# 12VDCDC.net
KiCad netlist of a schematic drawn in EAGLE
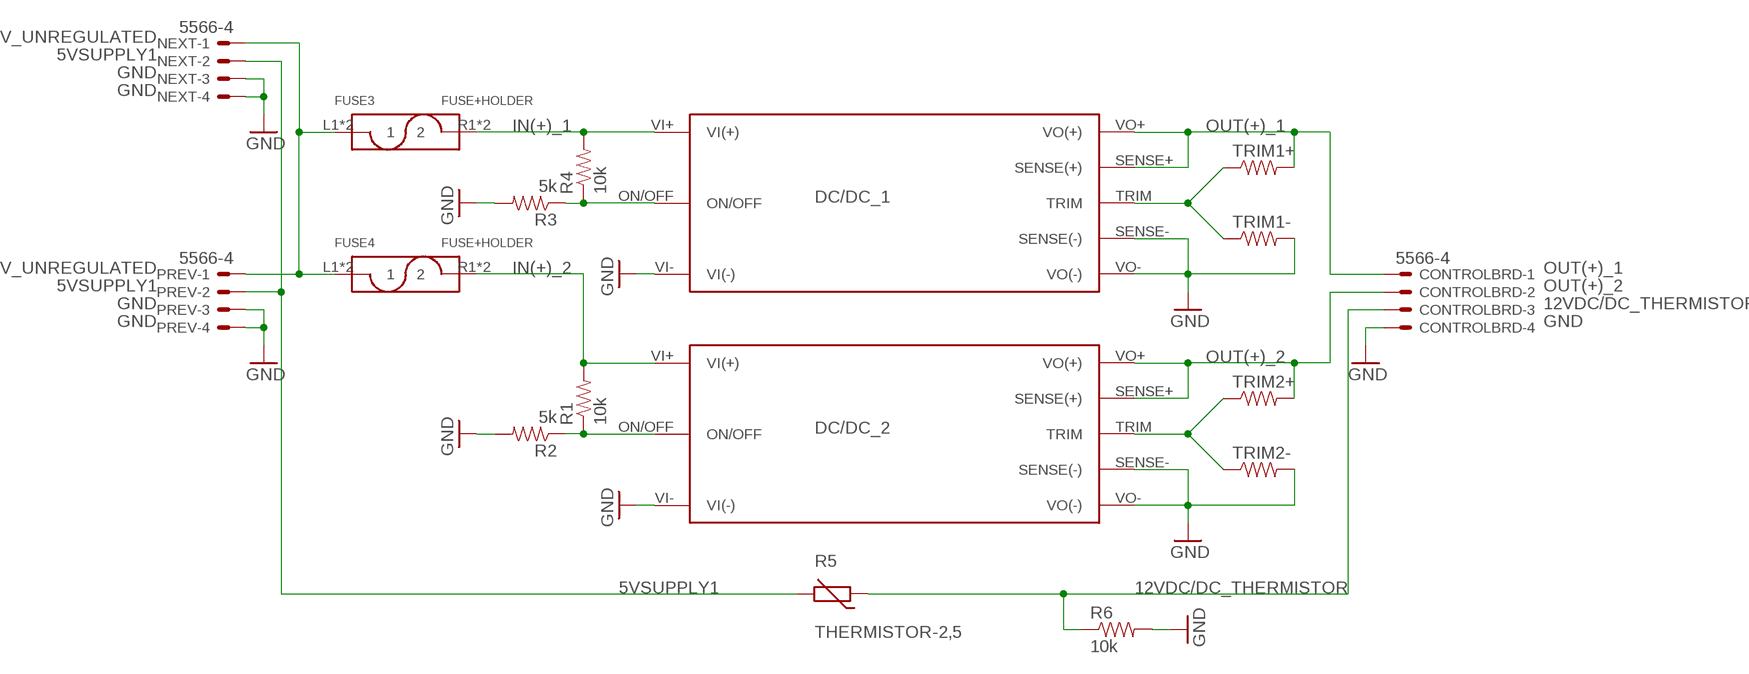
[diagram p0: schematic, sheet 1]

(export (version "E")
  (design (tool "Eeschema 10.0.6"))
  (components
    (comp (ref "CONTROLBRD")
      (value "5566-4")
      (footprint "eagle-import:5566-4")
      (libsource (lib "eagle-import") (part "5566-4"))
    )
    (comp (ref "DC/DC_1")
      (value "DC/DC-EIGHTH_BRICKEHHD006A0B41-HZ")
      (footprint "eagle-import:DC_DC-EIGHTH_BRICK")
      (libsource (lib "eagle-import") (part "DC/DC-EIGHTH_BRICKEHHD006A0B41-HZ"))
    )
    (comp (ref "DC/DC_2")
      (value "DC/DC-EIGHTH_BRICKEHHD006A0B41-HZ")
      (footprint "eagle-import:DC_DC-EIGHTH_BRICK")
      (libsource (lib "eagle-import") (part "DC/DC-EIGHTH_BRICKEHHD006A0B41-HZ"))
    )
    (comp (ref "FUSE3")
      (value "FUSE+HOLDER")
      (footprint "eagle-import:FUSE-HOLDER")
      (libsource (lib "eagle-import") (part "FUSE+HOLDER"))
    )
    (comp (ref "FUSE4")
      (value "FUSE+HOLDER")
      (footprint "eagle-import:FUSE-HOLDER")
      (libsource (lib "eagle-import") (part "FUSE+HOLDER"))
    )
    (comp (ref "NEXT")
      (value "5566-4")
      (footprint "eagle-import:5566-4")
      (libsource (lib "eagle-import") (part "5566-4"))
    )
    (comp (ref "PREV")
      (value "5566-4")
      (footprint "eagle-import:5566-4")
      (libsource (lib "eagle-import") (part "5566-4"))
    )
    (comp (ref "R1")
      (value "10k")
      (footprint "eagle-import:AXIAL-0.3")
      (libsource (lib "eagle-import") (part "RESISTORAXIAL-0.3"))
    )
    (comp (ref "R2")
      (value "5k")
      (footprint "eagle-import:AXIAL-0.3")
      (libsource (lib "eagle-import") (part "RESISTORAXIAL-0.3"))
    )
    (comp (ref "R3")
      (value "5k")
      (footprint "eagle-import:AXIAL-0.3")
      (libsource (lib "eagle-import") (part "RESISTORAXIAL-0.3"))
    )
    (comp (ref "R4")
      (value "10k")
      (footprint "eagle-import:AXIAL-0.3")
      (libsource (lib "eagle-import") (part "RESISTORAXIAL-0.3"))
    )
    (comp (ref "R5")
      (value "THERMISTOR-2,5")
      (footprint "eagle-import:RS-2,5")
      (libsource (lib "eagle-import") (part "THERMISTOR-2,5"))
    )
    (comp (ref "R6")
      (value "10k")
      (footprint "eagle-import:AXIAL-0.3")
      (libsource (lib "eagle-import") (part "RESISTORAXIAL-0.3"))
    )
    (comp (ref "TRIM1+")
      (value "RESISTORPTH-1/4W")
      (footprint "eagle-import:AXIAL-0.4")
      (libsource (lib "eagle-import") (part "RESISTORPTH-1/4W"))
    )
    (comp (ref "TRIM1-")
      (value "RESISTORPTH-1/4W")
      (footprint "eagle-import:AXIAL-0.4")
      (libsource (lib "eagle-import") (part "RESISTORPTH-1/4W"))
    )
    (comp (ref "TRIM2+")
      (value "RESISTORPTH-1/4W")
      (footprint "eagle-import:AXIAL-0.4")
      (libsource (lib "eagle-import") (part "RESISTORPTH-1/4W"))
    )
    (comp (ref "TRIM2-")
      (value "RESISTORPTH-1/4W")
      (footprint "eagle-import:AXIAL-0.4")
      (libsource (lib "eagle-import") (part "RESISTORPTH-1/4W"))
    )
  )
  (nets
    (net (code "1") (name "/5VSUPPLY1") (class "Default")
      (node (ref "NEXT") (pin "2") (pinfunction "S_2") (pintype "passive"))
      (node (ref "PREV") (pin "2") (pinfunction "S_2") (pintype "passive"))
      (node (ref "R5") (pin "2") (pinfunction "2_2") (pintype "passive"))
    )
    (net (code "2") (name "/12VDC{slash}DC_THERMISTOR") (class "Default")
      (node (ref "CONTROLBRD") (pin "3") (pinfunction "S_3") (pintype "passive"))
      (node (ref "R5") (pin "1") (pinfunction "1_1") (pintype "passive"))
      (node (ref "R6") (pin "P$1") (pinfunction "1_P$1") (pintype "passive"))
    )
    (net (code "3") (name "/IN(+)_1") (class "Default")
      (node (ref "DC/DC_1") (pin "VI+") (pinfunction "VI(+)_VI+") (pintype "bidirectional"))
      (node (ref "FUSE3") (pin "R1") (pinfunction "2_R1") (pintype "bidirectional"))
      (node (ref "FUSE3") (pin "R2") (pinfunction "2_R2") (pintype "bidirectional"))
      (node (ref "R4") (pin "P$2") (pinfunction "2_P$2") (pintype "passive"))
    )
    (net (code "4") (name "/IN(+)_2") (class "Default")
      (node (ref "DC/DC_2") (pin "VI+") (pinfunction "VI(+)_VI+") (pintype "bidirectional"))
      (node (ref "FUSE4") (pin "R1") (pinfunction "2_R1") (pintype "bidirectional"))
      (node (ref "FUSE4") (pin "R2") (pinfunction "2_R2") (pintype "bidirectional"))
      (node (ref "R1") (pin "P$2") (pinfunction "2_P$2") (pintype "passive"))
    )
    (net (code "5") (name "/LV_UNREGULATED") (class "Default")
      (node (ref "FUSE3") (pin "L1") (pinfunction "1_L1") (pintype "bidirectional"))
      (node (ref "FUSE3") (pin "L2") (pinfunction "1_L2") (pintype "bidirectional"))
      (node (ref "FUSE4") (pin "L1") (pinfunction "1_L1") (pintype "bidirectional"))
      (node (ref "FUSE4") (pin "L2") (pinfunction "1_L2") (pintype "bidirectional"))
      (node (ref "NEXT") (pin "1") (pinfunction "S_1") (pintype "passive"))
      (node (ref "PREV") (pin "1") (pinfunction "S_1") (pintype "passive"))
    )
    (net (code "6") (name "/OUT(+)_1") (class "Default")
      (node (ref "CONTROLBRD") (pin "1") (pinfunction "S_1") (pintype "passive"))
      (node (ref "DC/DC_1") (pin "SENSE+") (pinfunction "SENSE(+)_SENSE+") (pintype "bidirectional"))
      (node (ref "DC/DC_1") (pin "VO+") (pinfunction "VO(+)_VO+") (pintype "bidirectional"))
      (node (ref "TRIM1+") (pin "P$2") (pinfunction "2_P$2") (pintype "passive"))
    )
    (net (code "7") (name "/OUT(+)_2") (class "Default")
      (node (ref "CONTROLBRD") (pin "2") (pinfunction "S_2") (pintype "passive"))
      (node (ref "DC/DC_2") (pin "SENSE+") (pinfunction "SENSE(+)_SENSE+") (pintype "bidirectional"))
      (node (ref "DC/DC_2") (pin "VO+") (pinfunction "VO(+)_VO+") (pintype "bidirectional"))
      (node (ref "TRIM2+") (pin "P$2") (pinfunction "2_P$2") (pintype "passive"))
    )
    (net (code "8") (name "GND") (class "Default")
      (node (ref "CONTROLBRD") (pin "4") (pinfunction "S_4") (pintype "passive"))
      (node (ref "DC/DC_1") (pin "SENSE-") (pinfunction "SENSE(-)_SENSE-") (pintype "bidirectional"))
      (node (ref "DC/DC_1") (pin "VI-") (pinfunction "VI(-)_VI-") (pintype "bidirectional"))
      (node (ref "DC/DC_1") (pin "VO-") (pinfunction "VO(-)_VO-") (pintype "bidirectional"))
      (node (ref "DC/DC_2") (pin "SENSE-") (pinfunction "SENSE(-)_SENSE-") (pintype "bidirectional"))
      (node (ref "DC/DC_2") (pin "VI-") (pinfunction "VI(-)_VI-") (pintype "bidirectional"))
      (node (ref "DC/DC_2") (pin "VO-") (pinfunction "VO(-)_VO-") (pintype "bidirectional"))
      (node (ref "NEXT") (pin "3") (pinfunction "S_3") (pintype "passive"))
      (node (ref "NEXT") (pin "4") (pinfunction "S_4") (pintype "passive"))
      (node (ref "PREV") (pin "3") (pinfunction "S_3") (pintype "passive"))
      (node (ref "PREV") (pin "4") (pinfunction "S_4") (pintype "passive"))
      (node (ref "R2") (pin "P$2") (pinfunction "2_P$2") (pintype "passive"))
      (node (ref "R3") (pin "P$2") (pinfunction "2_P$2") (pintype "passive"))
      (node (ref "R6") (pin "P$2") (pinfunction "2_P$2") (pintype "passive"))
      (node (ref "TRIM1-") (pin "P$2") (pinfunction "2_P$2") (pintype "passive"))
      (node (ref "TRIM2-") (pin "P$2") (pinfunction "2_P$2") (pintype "passive"))
    )
    (net (code "9") (name "Net-(R1-1)") (class "Default")
      (node (ref "DC/DC_2") (pin "ON/OFF") (pinfunction "ON/OFF_ON/OFF") (pintype "bidirectional"))
      (node (ref "R1") (pin "P$1") (pinfunction "1_P$1") (pintype "passive"))
      (node (ref "R2") (pin "P$1") (pinfunction "1_P$1") (pintype "passive"))
    )
    (net (code "10") (name "Net-(R3-1)") (class "Default")
      (node (ref "DC/DC_1") (pin "ON/OFF") (pinfunction "ON/OFF_ON/OFF") (pintype "bidirectional"))
      (node (ref "R3") (pin "P$1") (pinfunction "1_P$1") (pintype "passive"))
      (node (ref "R4") (pin "P$1") (pinfunction "1_P$1") (pintype "passive"))
    )
    (net (code "11") (name "Net-(TRIM1+-1)") (class "Default")
      (node (ref "DC/DC_1") (pin "TRIM") (pinfunction "TRIM_TRIM") (pintype "bidirectional"))
      (node (ref "TRIM1+") (pin "P$1") (pinfunction "1_P$1") (pintype "passive"))
      (node (ref "TRIM1-") (pin "P$1") (pinfunction "1_P$1") (pintype "passive"))
    )
    (net (code "12") (name "Net-(TRIM2+-1)") (class "Default")
      (node (ref "DC/DC_2") (pin "TRIM") (pinfunction "TRIM_TRIM") (pintype "bidirectional"))
      (node (ref "TRIM2+") (pin "P$1") (pinfunction "1_P$1") (pintype "passive"))
      (node (ref "TRIM2-") (pin "P$1") (pinfunction "1_P$1") (pintype "passive"))
    )
  )
)
